# Follow_Line_Robot_Controller_Shematic.net
KiCad netlist of a schematic drawn in Altium Designer
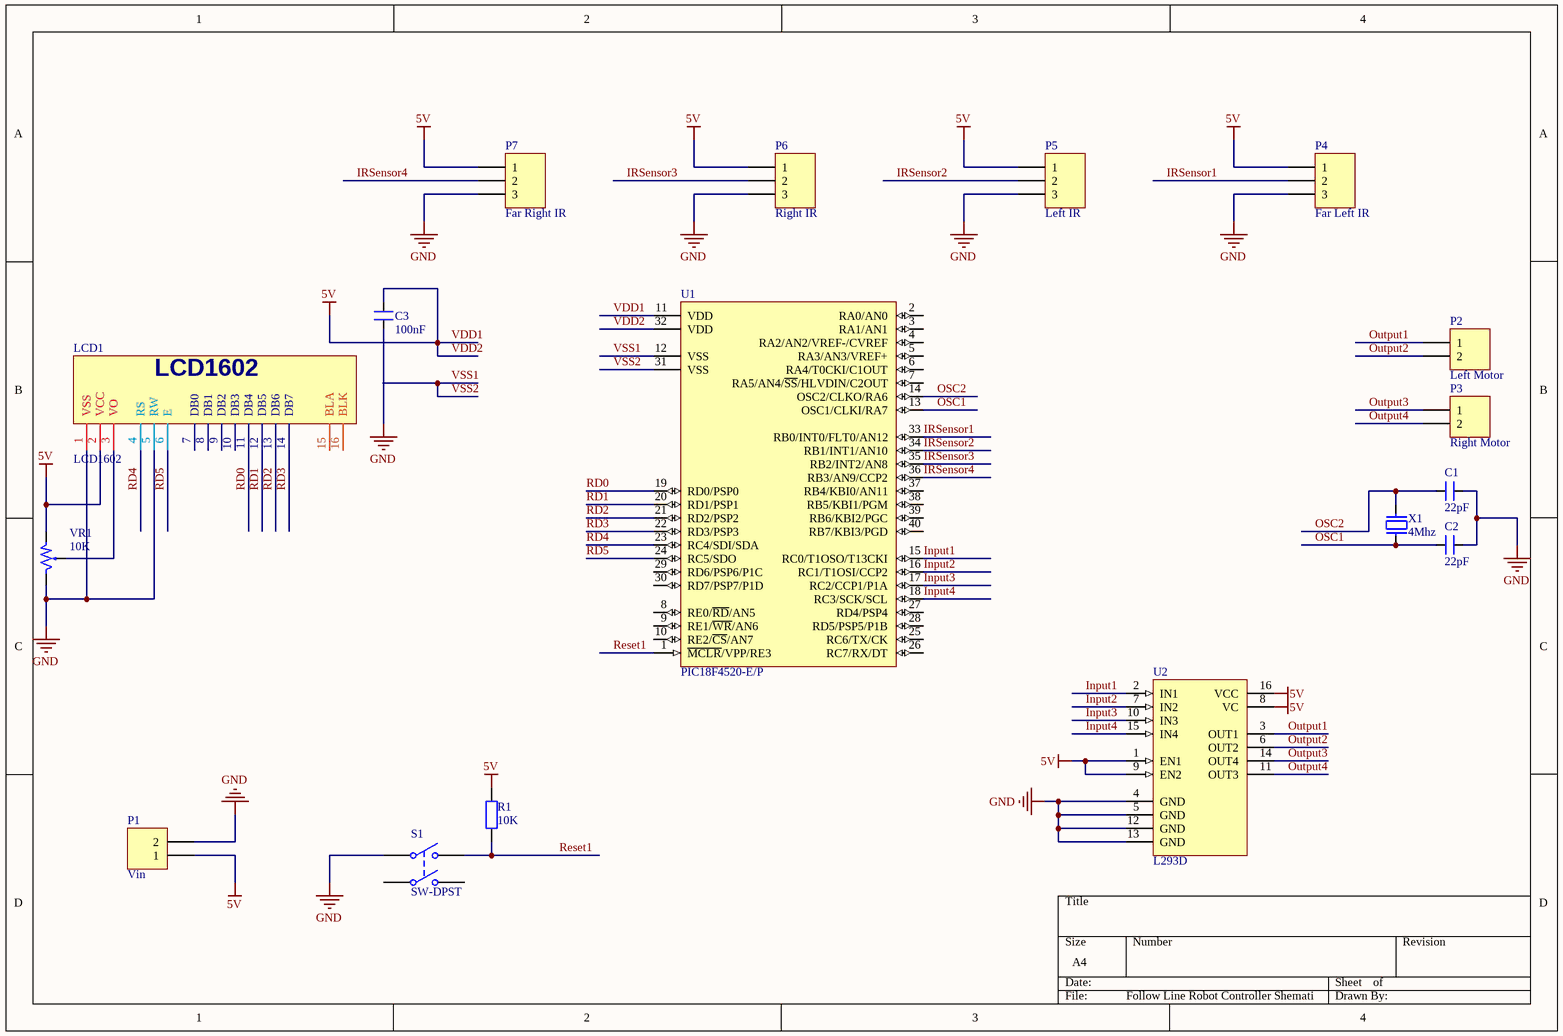
[diagram p0: Follow Line Robot Controller Shematic.SchDoc]

(export (version "E")
  (design (tool "Eeschema 10.0.6"))
  (components
    (comp (ref "C1")
      (value "22pF")
      (footprint "CN3")
      (description "Cap np W0.3")
      (fields (field (name "Comment") "Cap Cer"))
      (libsource (lib "Composants_Projet_Sheet_Full") (part "CN3"))
    )
    (comp (ref "C2")
      (value "22pF")
      (footprint "CN3")
      (description "Cap np W0.3")
      (fields (field (name "Comment") "Cap Cer"))
      (libsource (lib "Composants_Projet_Sheet_Full") (part "CN3"))
    )
    (comp (ref "C3")
      (value "100nF")
      (footprint "CN3")
      (description "Cap np W0.3")
      (fields (field (name "Comment") "Cap Cer"))
      (libsource (lib "Composants_Projet_Sheet_Full") (part "CN3"))
    )
    (comp (ref "LCD1")
      (value "LCD1602")
      (footprint "LCD1602")
      (libsource (lib "Composants_Projet_Sheet_Full") (part "LCD1602"))
    )
    (comp (ref "P1")
      (value "Vin")
      (footprint "HDR1X2")
      (description "Header, 2-Pin")
      (fields (field (name "PUBLISHER") "Altium Limited"))
      (libsource (lib "Composants_Projet_Sheet_Full") (part "Header 2"))
    )
    (comp (ref "P2")
      (value "Left Motor")
      (footprint "HDR1X2")
      (description "Header, 2-Pin")
      (fields (field (name "PUBLISHER") "Altium Limited"))
      (libsource (lib "") (part "Header 2_1"))
    )
    (comp (ref "P3")
      (value "Right Motor")
      (footprint "HDR1X2")
      (description "Header, 2-Pin")
      (fields (field (name "PUBLISHER") "Altium Limited"))
      (libsource (lib "") (part "Header 2_1"))
    )
    (comp (ref "P4")
      (value "Far Left IR")
      (footprint "HDR1X3")
      (description "Header, 3-Pin")
      (fields (field (name "PUBLISHER") "Altium Limited"))
      (libsource (lib "Composants_Projet_Sheet_Full") (part "Header 3"))
    )
    (comp (ref "P5")
      (value "Left IR")
      (footprint "HDR1X3")
      (description "Header, 3-Pin")
      (fields (field (name "PUBLISHER") "Altium Limited"))
      (libsource (lib "Composants_Projet_Sheet_Full") (part "Header 3"))
    )
    (comp (ref "P6")
      (value "Right IR")
      (footprint "HDR1X3")
      (description "Header, 3-Pin")
      (fields (field (name "PUBLISHER") "Altium Limited"))
      (libsource (lib "Composants_Projet_Sheet_Full") (part "Header 3"))
    )
    (comp (ref "P7")
      (value "Far Right IR")
      (footprint "HDR1X3")
      (description "Header, 3-Pin")
      (fields (field (name "PUBLISHER") "Altium Limited"))
      (libsource (lib "Composants_Projet_Sheet_Full") (part "Header 3"))
    )
    (comp (ref "R1")
      (value "10K")
      (footprint "Res")
      (description "Resistor")
      (fields (field (name "Comment") "RESET") (field (name "PUBLISHER") "Altium Limited"))
      (libsource (lib "Composants_Projet_Sheet_Full") (part "Res2"))
    )
    (comp (ref "S1")
      (value "SW-DPST")
      (footprint "DPST-4")
      (description "Double-Pole, Single-Throw Switch")
      (fields (field (name "PUBLISHER") "Altium Limited"))
      (libsource (lib "Composants_Projet_Sheet_Full") (part "SW-DPST"))
    )
    (comp (ref "U1")
      (value "PIC18F4520-E/P")
      (footprint "PIC18F-P40")
      (fields (field (name "PUBLISHER") "Altium Limited"))
      (libsource (lib "Composants_Projet_Sheet_Full") (part "PIC18F4520-E/P"))
    )
    (comp (ref "U2")
      (value "L293D")
      (footprint "DIP16")
      (description "Push-Pull Four Channel Driver With Diode")
      (fields (field (name "PUBLISHER") "Altium Limited"))
      (libsource (lib "Composants_Projet_Sheet_Full") (part "L293D"))
    )
    (comp (ref "VR1")
      (value "10K")
      (footprint "VR")
      (description "Var Resistor")
      (libsource (lib "Composants_Projet_Sheet_Full") (part "VR1"))
    )
    (comp (ref "X1")
      (value "4Mhz")
      (footprint "XT2")
      (description "Crystal For all Crystal 2pin.")
      (libsource (lib "Composants_Projet_Sheet_Full") (part "XT2"))
    )
  )
  (nets
    (net (code "1") (name "/IRSensor1") (class "Default")
      (node (ref "P4") (pin "2") (pinfunction "2_2") (pintype "passive"))
      (node (ref "U1") (pin "33") (pinfunction "RB0/INT0/FLT0/AN12_33") (pintype "bidirectional"))
    )
    (net (code "2") (name "/IRSensor2") (class "Default")
      (node (ref "P5") (pin "2") (pinfunction "2_2") (pintype "passive"))
      (node (ref "U1") (pin "34") (pinfunction "RB1/INT1/AN10_34") (pintype "bidirectional"))
    )
    (net (code "3") (name "/IRSensor3") (class "Default")
      (node (ref "P6") (pin "2") (pinfunction "2_2") (pintype "passive"))
      (node (ref "U1") (pin "35") (pinfunction "RB2/INT2/AN8_35") (pintype "bidirectional"))
    )
    (net (code "4") (name "/IRSensor4") (class "Default")
      (node (ref "P7") (pin "2") (pinfunction "2_2") (pintype "passive"))
      (node (ref "U1") (pin "36") (pinfunction "RB3/AN9/CCP2_36") (pintype "bidirectional"))
    )
    (net (code "5") (name "/Input1") (class "Default")
      (node (ref "U1") (pin "15") (pinfunction "RC0/T1OSO/T13CKI_15") (pintype "bidirectional"))
      (node (ref "U2") (pin "2") (pinfunction "IN1_2") (pintype "input"))
    )
    (net (code "6") (name "/Input2") (class "Default")
      (node (ref "U1") (pin "16") (pinfunction "RC1/T1OSI/CCP2_16") (pintype "bidirectional"))
      (node (ref "U2") (pin "7") (pinfunction "IN2_7") (pintype "input"))
    )
    (net (code "7") (name "/Input3") (class "Default")
      (node (ref "U1") (pin "17") (pinfunction "RC2/CCP1/P1A_17") (pintype "bidirectional"))
      (node (ref "U2") (pin "10") (pinfunction "IN3_10") (pintype "input"))
    )
    (net (code "8") (name "/Input4") (class "Default")
      (node (ref "U1") (pin "18") (pinfunction "RC3/SCK/SCL_18") (pintype "bidirectional"))
      (node (ref "U2") (pin "15") (pinfunction "IN4_15") (pintype "input"))
    )
    (net (code "9") (name "/OSC1") (class "Default")
      (node (ref "C2") (pin "1") (pinfunction "1_1") (pintype "passive"))
      (node (ref "U1") (pin "13") (pinfunction "OSC1/CLKI/RA7_13") (pintype "bidirectional"))
      (node (ref "X1") (pin "1") (pinfunction "1_1") (pintype "passive"))
    )
    (net (code "10") (name "/OSC2") (class "Default")
      (node (ref "C1") (pin "1") (pinfunction "1_1") (pintype "passive"))
      (node (ref "U1") (pin "14") (pinfunction "OSC2/CLKO/RA6_14") (pintype "bidirectional"))
      (node (ref "X1") (pin "2") (pinfunction "2_2") (pintype "passive"))
    )
    (net (code "11") (name "/Output1") (class "Default")
      (node (ref "P2") (pin "1") (pinfunction "1_1") (pintype "passive"))
      (node (ref "U2") (pin "3") (pinfunction "OUT1_3") (pintype "tri_state"))
    )
    (net (code "12") (name "/Output2") (class "Default")
      (node (ref "P2") (pin "2") (pinfunction "2_2") (pintype "passive"))
      (node (ref "U2") (pin "6") (pinfunction "OUT2_6") (pintype "tri_state"))
    )
    (net (code "13") (name "/Output3") (class "Default")
      (node (ref "P3") (pin "1") (pinfunction "1_1") (pintype "passive"))
      (node (ref "U2") (pin "14") (pinfunction "OUT4_14") (pintype "tri_state"))
    )
    (net (code "14") (name "/Output4") (class "Default")
      (node (ref "P3") (pin "2") (pinfunction "2_2") (pintype "passive"))
      (node (ref "U2") (pin "11") (pinfunction "OUT3_11") (pintype "tri_state"))
    )
    (net (code "15") (name "/RD0") (class "Default")
      (node (ref "LCD1") (pin "11") (pinfunction "DB4_11") (pintype "passive"))
      (node (ref "U1") (pin "19") (pinfunction "RD0/PSP0_19") (pintype "bidirectional"))
    )
    (net (code "16") (name "/RD1") (class "Default")
      (node (ref "LCD1") (pin "12") (pinfunction "DB5_12") (pintype "passive"))
      (node (ref "U1") (pin "20") (pinfunction "RD1/PSP1_20") (pintype "bidirectional"))
    )
    (net (code "17") (name "/RD2") (class "Default")
      (node (ref "LCD1") (pin "13") (pinfunction "DB6_13") (pintype "passive"))
      (node (ref "U1") (pin "21") (pinfunction "RD2/PSP2_21") (pintype "bidirectional"))
    )
    (net (code "18") (name "/RD3") (class "Default")
      (node (ref "LCD1") (pin "14") (pinfunction "DB7_14") (pintype "passive"))
      (node (ref "U1") (pin "22") (pinfunction "RD3/PSP3_22") (pintype "bidirectional"))
    )
    (net (code "19") (name "/RD4") (class "Default")
      (node (ref "LCD1") (pin "4") (pinfunction "RS_4") (pintype "passive"))
      (node (ref "U1") (pin "23") (pinfunction "RC4/SDI/SDA_23") (pintype "bidirectional"))
    )
    (net (code "20") (name "/RD5") (class "Default")
      (node (ref "LCD1") (pin "6") (pinfunction "E_6") (pintype "passive"))
      (node (ref "U1") (pin "24") (pinfunction "RC5/SDO_24") (pintype "bidirectional"))
    )
    (net (code "21") (name "/Reset1") (class "Default")
      (node (ref "R1") (pin "1") (pinfunction "1_1") (pintype "passive"))
      (node (ref "S1") (pin "2") (pinfunction "NO1_2") (pintype "passive"))
      (node (ref "U1") (pin "1") (pinfunction "~{MCLR}/VPP/RE3_1") (pintype "input"))
    )
    (net (code "22") (name "/VSS1") (class "Default")
      (node (ref "U1") (pin "12") (pinfunction "VSS_12") (pintype "power_in"))
      (node (ref "U1") (pin "31") (pinfunction "VSS_31") (pintype "power_in"))
    )
    (net (code "23") (name "5V") (class "Default")
      (node (ref "C3") (pin "2") (pinfunction "2_2") (pintype "passive"))
      (node (ref "LCD1") (pin "2") (pinfunction "VCC_2") (pintype "passive"))
      (node (ref "P1") (pin "1") (pinfunction "1_1") (pintype "passive"))
      (node (ref "P4") (pin "1") (pinfunction "1_1") (pintype "passive"))
      (node (ref "P5") (pin "1") (pinfunction "1_1") (pintype "passive"))
      (node (ref "P6") (pin "1") (pinfunction "1_1") (pintype "passive"))
      (node (ref "P7") (pin "1") (pinfunction "1_1") (pintype "passive"))
      (node (ref "R1") (pin "2") (pinfunction "2_2") (pintype "passive"))
      (node (ref "U1") (pin "11") (pinfunction "VDD_11") (pintype "power_in"))
      (node (ref "U1") (pin "32") (pinfunction "VDD_32") (pintype "power_in"))
      (node (ref "U2") (pin "1") (pinfunction "EN1_1") (pintype "input"))
      (node (ref "U2") (pin "16") (pinfunction "VCC_16") (pintype "power_in"))
      (node (ref "U2") (pin "8") (pinfunction "VC_8") (pintype "power_in"))
      (node (ref "U2") (pin "9") (pinfunction "EN2_9") (pintype "input"))
      (node (ref "VR1") (pin "1") (pinfunction "1_1") (pintype "passive"))
    )
    (net (code "24") (name "GND") (class "Default")
      (node (ref "C1") (pin "2") (pinfunction "2_2") (pintype "passive"))
      (node (ref "C2") (pin "2") (pinfunction "2_2") (pintype "passive"))
      (node (ref "C3") (pin "1") (pinfunction "1_1") (pintype "passive"))
      (node (ref "LCD1") (pin "1") (pinfunction "VSS_1") (pintype "passive"))
      (node (ref "LCD1") (pin "5") (pinfunction "RW_5") (pintype "passive"))
      (node (ref "P1") (pin "2") (pinfunction "2_2") (pintype "passive"))
      (node (ref "P4") (pin "3") (pinfunction "3_3") (pintype "passive"))
      (node (ref "P5") (pin "3") (pinfunction "3_3") (pintype "passive"))
      (node (ref "P6") (pin "3") (pinfunction "3_3") (pintype "passive"))
      (node (ref "P7") (pin "3") (pinfunction "3_3") (pintype "passive"))
      (node (ref "S1") (pin "1") (pinfunction "COMMON1_1") (pintype "passive"))
      (node (ref "U2") (pin "12") (pinfunction "GND_12") (pintype "power_in"))
      (node (ref "U2") (pin "13") (pinfunction "GND_13") (pintype "power_in"))
      (node (ref "U2") (pin "4") (pinfunction "GND_4") (pintype "power_in"))
      (node (ref "U2") (pin "5") (pinfunction "GND_5") (pintype "power_in"))
      (node (ref "VR1") (pin "3") (pinfunction "3_3") (pintype "passive"))
    )
    (net (code "25") (name "Net-(LCD1-VO)") (class "Default")
      (node (ref "LCD1") (pin "3") (pinfunction "VO_3") (pintype "passive"))
      (node (ref "VR1") (pin "2") (pinfunction "2_2") (pintype "passive"))
    )
    (net (code "26") (name "unconnected-(LCD1-BLA-Pad15)") (class "Default")
      (node (ref "LCD1") (pin "15") (pinfunction "BLA_15") (pintype "passive"))
    )
    (net (code "27") (name "unconnected-(LCD1-BLK-Pad16)") (class "Default")
      (node (ref "LCD1") (pin "16") (pinfunction "BLK_16") (pintype "passive"))
    )
    (net (code "28") (name "unconnected-(LCD1-DB0-Pad7)") (class "Default")
      (node (ref "LCD1") (pin "7") (pinfunction "DB0_7") (pintype "passive"))
    )
    (net (code "29") (name "unconnected-(LCD1-DB1-Pad8)") (class "Default")
      (node (ref "LCD1") (pin "8") (pinfunction "DB1_8") (pintype "passive"))
    )
    (net (code "30") (name "unconnected-(LCD1-DB2-Pad9)") (class "Default")
      (node (ref "LCD1") (pin "9") (pinfunction "DB2_9") (pintype "passive"))
    )
    (net (code "31") (name "unconnected-(LCD1-DB3-Pad10)") (class "Default")
      (node (ref "LCD1") (pin "10") (pinfunction "DB3_10") (pintype "passive"))
    )
    (net (code "32") (name "unconnected-(S1-COMMON2-Pad3)") (class "Default")
      (node (ref "S1") (pin "3") (pinfunction "COMMON2_3") (pintype "passive"))
    )
    (net (code "33") (name "unconnected-(S1-NO2-Pad4)") (class "Default")
      (node (ref "S1") (pin "4") (pinfunction "NO2_4") (pintype "passive"))
    )
    (net (code "34") (name "unconnected-(U1-RA0{slash}AN0-Pad2)") (class "Default")
      (node (ref "U1") (pin "2") (pinfunction "RA0/AN0_2") (pintype "bidirectional"))
    )
    (net (code "35") (name "unconnected-(U1-RA1{slash}AN1-Pad3)") (class "Default")
      (node (ref "U1") (pin "3") (pinfunction "RA1/AN1_3") (pintype "bidirectional"))
    )
    (net (code "36") (name "unconnected-(U1-RA2{slash}AN2{slash}VREF-{slash}CVREF-Pad4)") (class "Default")
      (node (ref "U1") (pin "4") (pinfunction "RA2/AN2/VREF-/CVREF_4") (pintype "bidirectional"))
    )
    (net (code "37") (name "unconnected-(U1-RA3{slash}AN3{slash}VREF+-Pad5)") (class "Default")
      (node (ref "U1") (pin "5") (pinfunction "RA3/AN3/VREF+_5") (pintype "bidirectional"))
    )
    (net (code "38") (name "unconnected-(U1-RA4{slash}T0CKI{slash}C1OUT-Pad6)") (class "Default")
      (node (ref "U1") (pin "6") (pinfunction "RA4/T0CKI/C1OUT_6") (pintype "bidirectional"))
    )
    (net (code "39") (name "unconnected-(U1-RA5{slash}AN4{slash}~{SS}{slash}HLVDIN{slash}C2OUT-Pad7)") (class "Default")
      (node (ref "U1") (pin "7") (pinfunction "RA5/AN4/~{SS}/HLVDIN/C2OUT_7") (pintype "bidirectional"))
    )
    (net (code "40") (name "unconnected-(U1-RB4{slash}KBI0{slash}AN11-Pad37)") (class "Default")
      (node (ref "U1") (pin "37") (pinfunction "RB4/KBI0/AN11_37") (pintype "bidirectional"))
    )
    (net (code "41") (name "unconnected-(U1-RB5{slash}KBI1{slash}PGM-Pad38)") (class "Default")
      (node (ref "U1") (pin "38") (pinfunction "RB5/KBI1/PGM_38") (pintype "bidirectional"))
    )
    (net (code "42") (name "unconnected-(U1-RB6{slash}KBI2{slash}PGC-Pad39)") (class "Default")
      (node (ref "U1") (pin "39") (pinfunction "RB6/KBI2/PGC_39") (pintype "bidirectional"))
    )
    (net (code "43") (name "unconnected-(U1-RB7{slash}KBI3{slash}PGD-Pad40)") (class "Default")
      (node (ref "U1") (pin "40") (pinfunction "RB7/KBI3/PGD_40") (pintype "bidirectional"))
    )
    (net (code "44") (name "unconnected-(U1-RC6{slash}TX{slash}CK-Pad25)") (class "Default")
      (node (ref "U1") (pin "25") (pinfunction "RC6/TX/CK_25") (pintype "bidirectional"))
    )
    (net (code "45") (name "unconnected-(U1-RC7{slash}RX{slash}DT-Pad26)") (class "Default")
      (node (ref "U1") (pin "26") (pinfunction "RC7/RX/DT_26") (pintype "bidirectional"))
    )
    (net (code "46") (name "unconnected-(U1-RD4{slash}PSP4-Pad27)") (class "Default")
      (node (ref "U1") (pin "27") (pinfunction "RD4/PSP4_27") (pintype "bidirectional"))
    )
    (net (code "47") (name "unconnected-(U1-RD5{slash}PSP5{slash}P1B-Pad28)") (class "Default")
      (node (ref "U1") (pin "28") (pinfunction "RD5/PSP5/P1B_28") (pintype "bidirectional"))
    )
    (net (code "48") (name "unconnected-(U1-RD6{slash}PSP6{slash}P1C-Pad29)") (class "Default")
      (node (ref "U1") (pin "29") (pinfunction "RD6/PSP6/P1C_29") (pintype "bidirectional"))
    )
    (net (code "49") (name "unconnected-(U1-RD7{slash}PSP7{slash}P1D-Pad30)") (class "Default")
      (node (ref "U1") (pin "30") (pinfunction "RD7/PSP7/P1D_30") (pintype "bidirectional"))
    )
    (net (code "50") (name "unconnected-(U1-RE0{slash}~{RD}{slash}AN5-Pad8)") (class "Default")
      (node (ref "U1") (pin "8") (pinfunction "RE0/~{RD}/AN5_8") (pintype "bidirectional"))
    )
    (net (code "51") (name "unconnected-(U1-RE1{slash}~{WR}{slash}AN6-Pad9)") (class "Default")
      (node (ref "U1") (pin "9") (pinfunction "RE1/~{WR}/AN6_9") (pintype "bidirectional"))
    )
    (net (code "52") (name "unconnected-(U1-RE2{slash}~{CS}{slash}AN7-Pad10)") (class "Default")
      (node (ref "U1") (pin "10") (pinfunction "RE2/~{CS}/AN7_10") (pintype "bidirectional"))
    )
  )
)
